# TMC2130.net
KiCad netlist of a schematic drawn in Altium Designer
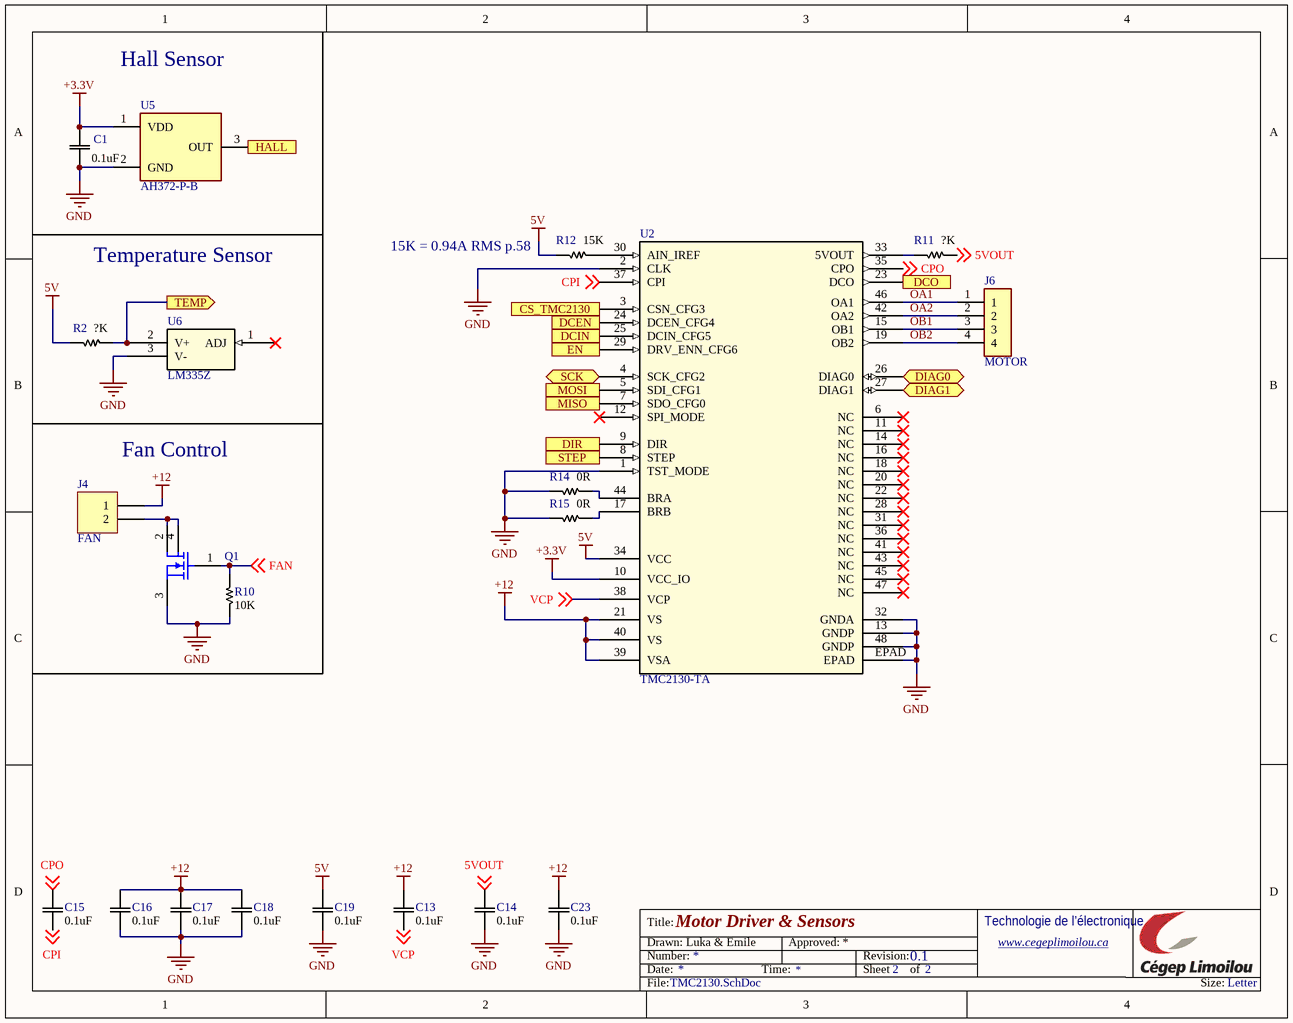
[diagram p0: TMC2130.SchDoc]

(export (version "E")
  (design (tool "Eeschema 10.0.6"))
  (components
    (comp (ref "C1")
      (value "0.1uF")
      (footprint "0603")
      (description "Capacitor SMD 0603")
      (fields
        (field (name "MANUFACTURER_PART_NUMBER") "12065A820JAT2A")
        (field (name "Comment") "Capacitor SMD")
        (field (name "COPYRIGHT") "Copyright (C) 2018 Accelerated Designs. All rights reserved")
      )
      (libsource (lib "Schematic_Emile") (part "Capacitor SMD"))
    )
    (comp (ref "C13")
      (value "0.1uF")
      (footprint "0603")
      (description "Capacitor SMD 0603")
      (fields
        (field (name "MANUFACTURER_PART_NUMBER") "12065A820JAT2A")
        (field (name "Comment") "Capacitor SMD")
        (field (name "COPYRIGHT") "Copyright (C) 2018 Accelerated Designs. All rights reserved")
      )
      (libsource (lib "Schematic_Emile") (part "Capacitor SMD"))
    )
    (comp (ref "C14")
      (value "0.1uF")
      (footprint "0603")
      (description "Capacitor SMD 0603")
      (fields
        (field (name "MANUFACTURER_PART_NUMBER") "12065A820JAT2A")
        (field (name "Comment") "Capacitor SMD")
        (field (name "COPYRIGHT") "Copyright (C) 2018 Accelerated Designs. All rights reserved")
      )
      (libsource (lib "Schematic_Emile") (part "Capacitor SMD"))
    )
    (comp (ref "C15")
      (value "0.1uF")
      (footprint "0603")
      (description "Capacitor SMD 0603")
      (fields
        (field (name "MANUFACTURER_PART_NUMBER") "12065A820JAT2A")
        (field (name "Comment") "Capacitor SMD")
        (field (name "COPYRIGHT") "Copyright (C) 2018 Accelerated Designs. All rights reserved")
      )
      (libsource (lib "Schematic_Emile") (part "Capacitor SMD"))
    )
    (comp (ref "C16")
      (value "0.1uF")
      (footprint "0603")
      (description "Capacitor SMD 0603")
      (fields
        (field (name "MANUFACTURER_PART_NUMBER") "12065A820JAT2A")
        (field (name "Comment") "Capacitor SMD")
        (field (name "COPYRIGHT") "Copyright (C) 2018 Accelerated Designs. All rights reserved")
      )
      (libsource (lib "Schematic_Emile") (part "Capacitor SMD"))
    )
    (comp (ref "C17")
      (value "0.1uF")
      (footprint "0603")
      (description "Capacitor SMD 0603")
      (fields
        (field (name "MANUFACTURER_PART_NUMBER") "12065A820JAT2A")
        (field (name "Comment") "Capacitor SMD")
        (field (name "COPYRIGHT") "Copyright (C) 2018 Accelerated Designs. All rights reserved")
      )
      (libsource (lib "Schematic_Emile") (part "Capacitor SMD"))
    )
    (comp (ref "C18")
      (value "0.1uF")
      (footprint "0603")
      (description "Capacitor SMD 0603")
      (fields
        (field (name "MANUFACTURER_PART_NUMBER") "12065A820JAT2A")
        (field (name "Comment") "Capacitor SMD")
        (field (name "COPYRIGHT") "Copyright (C) 2018 Accelerated Designs. All rights reserved")
      )
      (libsource (lib "Schematic_Emile") (part "Capacitor SMD"))
    )
    (comp (ref "C19")
      (value "0.1uF")
      (footprint "0603")
      (description "Capacitor SMD 0603")
      (fields
        (field (name "MANUFACTURER_PART_NUMBER") "12065A820JAT2A")
        (field (name "Comment") "Capacitor SMD")
        (field (name "COPYRIGHT") "Copyright (C) 2018 Accelerated Designs. All rights reserved")
      )
      (libsource (lib "Schematic_Emile") (part "Capacitor SMD"))
    )
    (comp (ref "C23")
      (value "0.1uF")
      (footprint "0603")
      (description "Capacitor SMD 0603")
      (fields
        (field (name "MANUFACTURER_PART_NUMBER") "12065A820JAT2A")
        (field (name "Comment") "Capacitor SMD")
        (field (name "COPYRIGHT") "Copyright (C) 2018 Accelerated Designs. All rights reserved")
      )
      (libsource (lib "Schematic_Emile") (part "Capacitor SMD"))
    )
    (comp (ref "J4")
      (value "FAN")
      (footprint "HDR1X2")
      (description "Header, 2-Pin")
      (fields (field (name "PUBLISHER") "Altium Limited"))
      (libsource (lib "Miscellaneous Connectors") (part "Header 2"))
    )
    (comp (ref "J6")
      (value "MOTOR")
      (footprint "JST 4POS 2.5mm 90°")
      (description "Connector")
      (fields
        (field (name "MANUFACTURER_PART_NUMBER") "S4B-XH-A(LF)(SN)")
        (field (name "RS PART NUMBER") "8201589P")
      )
      (libsource (lib "Schematic_Emile") (part "JST 4POS"))
    )
    (comp (ref "Q1")
      (value "MOSFET N-CH")
      (footprint "SOT223_M")
      (description "55V 7A SOT223")
      (libsource (lib "Schematic_Emile") (part "MOSFET N-CH"))
    )
    (comp (ref "R2")
      (value "?K")
      (footprint "0603")
      (description "Resistor 0603 SMD")
      (fields
        (field (name "MANUFACTURER_PART_NUMBER") "ERJ8CWFR024V")
        (field (name "Comment") "Resistor 0603")
        (field (name "COPYRIGHT") "Copyright (C) 2018 Accelerated Designs. All rights reserved")
      )
      (libsource (lib "Schematic_Emile") (part "Resistor 0603"))
    )
    (comp (ref "R10")
      (value "10K")
      (footprint "0603")
      (description "Resistor 0603 SMD")
      (fields
        (field (name "MANUFACTURER_PART_NUMBER") "ERJ8CWFR024V")
        (field (name "Comment") "Resistor 0603")
        (field (name "COPYRIGHT") "Copyright (C) 2018 Accelerated Designs. All rights reserved")
      )
      (libsource (lib "Schematic_Emile") (part "Resistor 0603"))
    )
    (comp (ref "R11")
      (value "?K")
      (footprint "0603")
      (description "Resistor 0603 SMD")
      (fields
        (field (name "MANUFACTURER_PART_NUMBER") "ERJ8CWFR024V")
        (field (name "Comment") "Resistor 0603")
        (field (name "COPYRIGHT") "Copyright (C) 2018 Accelerated Designs. All rights reserved")
      )
      (libsource (lib "Schematic_Emile") (part "Resistor 0603"))
    )
    (comp (ref "R12")
      (value "15K")
      (footprint "0603")
      (description "Resistor 0603 SMD")
      (fields
        (field (name "MANUFACTURER_PART_NUMBER") "ERJ8CWFR024V")
        (field (name "Comment") "Resistor 0603")
        (field (name "COPYRIGHT") "Copyright (C) 2018 Accelerated Designs. All rights reserved")
      )
      (libsource (lib "Schematic_Emile") (part "Resistor 0603"))
    )
    (comp (ref "R14")
      (value "0R")
      (footprint "0603")
      (description "Resistor 0603 SMD")
      (fields
        (field (name "MANUFACTURER_PART_NUMBER") "ERJ8CWFR024V")
        (field (name "Comment") "Resistor 0603")
        (field (name "COPYRIGHT") "Copyright (C) 2018 Accelerated Designs. All rights reserved")
      )
      (libsource (lib "Schematic_Emile") (part "Resistor 0603"))
    )
    (comp (ref "R15")
      (value "0R")
      (footprint "0603")
      (description "Resistor 0603 SMD")
      (fields
        (field (name "MANUFACTURER_PART_NUMBER") "ERJ8CWFR024V")
        (field (name "Comment") "Resistor 0603")
        (field (name "COPYRIGHT") "Copyright (C) 2018 Accelerated Designs. All rights reserved")
      )
      (libsource (lib "Schematic_Emile") (part "Resistor 0603"))
    )
    (comp (ref "U2")
      (value "TMC2130-TA")
      (footprint "eTQFP48_9x9")
      (description "Motor Driver TMC2130")
      (fields (field (name "COPYRIGHT") "Copyright (C) 2016 Accelerated Designs. All rights reserved"))
      (libsource (lib "Schematic_Emile") (part "TMC2130-TA"))
    )
    (comp (ref "U5")
      (value "AH372-P-B")
      (footprint "Footprint_Emile:AH372PB")
      (description "Hall Sensor")
      (fields (field (name "MOUSER PART NUMBER") "621-AH372-P-B") (field (name "RS PART NUMBER") "1333361P"))
      (libsource (lib "Schematic_Emile") (part "AH372-P-B"))
    )
    (comp (ref "U6")
      (value "LM335Z")
      (footprint "TO92")
      (description "Temperature Sensor")
      (fields (field (name "COPYRIGHT") "Copyright (C) 2018 Accelerated Designs. All rights reserved"))
      (libsource (lib "Schematic_Emile") (part "LM335Z"))
    )
  )
  (nets
    (net (code "1") (name "+3.3V") (class "Default")
      (node (ref "C1") (pin "2") (pinfunction "2_2") (pintype "passive"))
      (node (ref "U2") (pin "10") (pinfunction "VCC_IO_10") (pintype "power_in"))
      (node (ref "U5") (pin "1") (pinfunction "VDD_1") (pintype "passive"))
    )
    (net (code "2") (name "+12") (class "Default")
      (node (ref "C13") (pin "2") (pinfunction "2_2") (pintype "passive"))
      (node (ref "C16") (pin "2") (pinfunction "2_2") (pintype "passive"))
      (node (ref "C17") (pin "2") (pinfunction "2_2") (pintype "passive"))
      (node (ref "C18") (pin "2") (pinfunction "2_2") (pintype "passive"))
      (node (ref "C23") (pin "2") (pinfunction "2_2") (pintype "passive"))
      (node (ref "J4") (pin "1") (pinfunction "1_1") (pintype "passive"))
      (node (ref "U2") (pin "21") (pinfunction "VS_21") (pintype "power_in"))
      (node (ref "U2") (pin "39") (pinfunction "VSA_39") (pintype "power_in"))
      (node (ref "U2") (pin "40") (pinfunction "VS_40") (pintype "power_in"))
    )
    (net (code "3") (name "/CS_TMC2130") (class "Default")
      (node (ref "U2") (pin "3") (pinfunction "CSN_CFG3_3") (pintype "input"))
    )
    (net (code "4") (name "/DCEN") (class "Default")
      (node (ref "U2") (pin "24") (pinfunction "DCEN_CFG4_24") (pintype "input"))
    )
    (net (code "5") (name "/DCIN") (class "Default")
      (node (ref "U2") (pin "25") (pinfunction "DCIN_CFG5_25") (pintype "input"))
    )
    (net (code "6") (name "/DCO") (class "Default")
      (node (ref "U2") (pin "23") (pinfunction "DCO_23") (pintype "output"))
    )
    (net (code "7") (name "/DIAG0") (class "Default")
      (node (ref "U2") (pin "26") (pinfunction "DIAG0_26") (pintype "bidirectional"))
    )
    (net (code "8") (name "/DIAG1") (class "Default")
      (node (ref "U2") (pin "27") (pinfunction "DIAG1_27") (pintype "bidirectional"))
    )
    (net (code "9") (name "/DIR") (class "Default")
      (node (ref "U2") (pin "9") (pinfunction "DIR_9") (pintype "input"))
    )
    (net (code "10") (name "/EN") (class "Default")
      (node (ref "U2") (pin "29") (pinfunction "DRV_ENN_CFG6_29") (pintype "input"))
    )
    (net (code "11") (name "/HALL") (class "Default")
      (node (ref "U5") (pin "3") (pinfunction "OUT_3") (pintype "passive"))
    )
    (net (code "12") (name "/MISO") (class "Default")
      (node (ref "U2") (pin "7") (pinfunction "SDO_CFG0_7") (pintype "input"))
    )
    (net (code "13") (name "/MOSI") (class "Default")
      (node (ref "U2") (pin "5") (pinfunction "SDI_CFG1_5") (pintype "input"))
    )
    (net (code "14") (name "/OA1") (class "Default")
      (node (ref "J6") (pin "1") (pinfunction "1_1") (pintype "passive"))
      (node (ref "U2") (pin "46") (pinfunction "OA1_46") (pintype "output"))
    )
    (net (code "15") (name "/OA2") (class "Default")
      (node (ref "J6") (pin "2") (pinfunction "2_2") (pintype "passive"))
      (node (ref "U2") (pin "42") (pinfunction "OA2_42") (pintype "output"))
    )
    (net (code "16") (name "/OB1") (class "Default")
      (node (ref "J6") (pin "3") (pinfunction "3_3") (pintype "passive"))
      (node (ref "U2") (pin "15") (pinfunction "OB1_15") (pintype "output"))
    )
    (net (code "17") (name "/OB2") (class "Default")
      (node (ref "J6") (pin "4") (pinfunction "4_4") (pintype "passive"))
      (node (ref "U2") (pin "19") (pinfunction "OB2_19") (pintype "output"))
    )
    (net (code "18") (name "/SCK") (class "Default")
      (node (ref "U2") (pin "4") (pinfunction "SCK_CFG2_4") (pintype "input"))
    )
    (net (code "19") (name "/STEP") (class "Default")
      (node (ref "U2") (pin "8") (pinfunction "STEP_8") (pintype "input"))
    )
    (net (code "20") (name "/TEMP") (class "Default")
      (node (ref "R2") (pin "2") (pinfunction "2_2") (pintype "passive"))
      (node (ref "U6") (pin "2") (pinfunction "V+_2") (pintype "power_in"))
    )
    (net (code "21") (name "5V") (class "Default")
      (node (ref "C19") (pin "2") (pinfunction "2_2") (pintype "passive"))
      (node (ref "R12") (pin "1") (pinfunction "1_1") (pintype "passive"))
      (node (ref "R2") (pin "1") (pinfunction "1_1") (pintype "passive"))
      (node (ref "U2") (pin "34") (pinfunction "VCC_34") (pintype "power_in"))
    )
    (net (code "22") (name "5VOUT") (class "Default")
      (node (ref "C14") (pin "2") (pinfunction "2_2") (pintype "passive"))
      (node (ref "R11") (pin "2") (pinfunction "2_2") (pintype "passive"))
    )
    (net (code "23") (name "CPI") (class "Default")
      (node (ref "C15") (pin "1") (pinfunction "1_1") (pintype "passive"))
      (node (ref "U2") (pin "37") (pinfunction "CPI_37") (pintype "input"))
    )
    (net (code "24") (name "CPO") (class "Default")
      (node (ref "C15") (pin "2") (pinfunction "2_2") (pintype "passive"))
      (node (ref "U2") (pin "35") (pinfunction "CPO_35") (pintype "output"))
    )
    (net (code "25") (name "FAN") (class "Default")
      (node (ref "Q1") (pin "1") (pinfunction "G_1") (pintype "passive"))
      (node (ref "R10") (pin "2") (pinfunction "2_2") (pintype "passive"))
    )
    (net (code "26") (name "GND") (class "Default")
      (node (ref "C1") (pin "1") (pinfunction "1_1") (pintype "passive"))
      (node (ref "C14") (pin "1") (pinfunction "1_1") (pintype "passive"))
      (node (ref "C16") (pin "1") (pinfunction "1_1") (pintype "passive"))
      (node (ref "C17") (pin "1") (pinfunction "1_1") (pintype "passive"))
      (node (ref "C18") (pin "1") (pinfunction "1_1") (pintype "passive"))
      (node (ref "C19") (pin "1") (pinfunction "1_1") (pintype "passive"))
      (node (ref "C23") (pin "1") (pinfunction "1_1") (pintype "passive"))
      (node (ref "Q1") (pin "3") (pinfunction "S_3") (pintype "passive"))
      (node (ref "R10") (pin "1") (pinfunction "1_1") (pintype "passive"))
      (node (ref "R14") (pin "1") (pinfunction "1_1") (pintype "passive"))
      (node (ref "R15") (pin "1") (pinfunction "1_1") (pintype "passive"))
      (node (ref "U2") (pin "1") (pinfunction "TST_MODE_1") (pintype "input"))
      (node (ref "U2") (pin "13") (pinfunction "GNDP_13") (pintype "power_in"))
      (node (ref "U2") (pin "2") (pinfunction "CLK_2") (pintype "input"))
      (node (ref "U2") (pin "32") (pinfunction "GNDA_32") (pintype "power_in"))
      (node (ref "U2") (pin "48") (pinfunction "GNDP_48") (pintype "power_in"))
      (node (ref "U2") (pin "EPAD") (pinfunction "EPAD_EPAD") (pintype "passive"))
      (node (ref "U5") (pin "2") (pinfunction "GND_2") (pintype "passive"))
      (node (ref "U6") (pin "3") (pinfunction "V-_3") (pintype "power_in"))
    )
    (net (code "27") (name "Net-(J4-Pad2)") (class "Default")
      (node (ref "J4") (pin "2") (pinfunction "2_2") (pintype "passive"))
      (node (ref "Q1") (pin "2") (pinfunction "D_2") (pintype "passive"))
      (node (ref "Q1") (pin "4") (pinfunction "D_4") (pintype "passive"))
    )
    (net (code "28") (name "Net-(U2-5VOUT)") (class "Default")
      (node (ref "R11") (pin "1") (pinfunction "1_1") (pintype "passive"))
      (node (ref "U2") (pin "33") (pinfunction "5VOUT_33") (pintype "output"))
    )
    (net (code "29") (name "Net-(U2-AIN_IREF)") (class "Default")
      (node (ref "R12") (pin "2") (pinfunction "2_2") (pintype "passive"))
      (node (ref "U2") (pin "30") (pinfunction "AIN_IREF_30") (pintype "input"))
    )
    (net (code "30") (name "Net-(U2-BRA)") (class "Default")
      (node (ref "R14") (pin "2") (pinfunction "2_2") (pintype "passive"))
      (node (ref "U2") (pin "44") (pinfunction "BRA_44") (pintype "passive"))
    )
    (net (code "31") (name "Net-(U2-BRB)") (class "Default")
      (node (ref "R15") (pin "2") (pinfunction "2_2") (pintype "passive"))
      (node (ref "U2") (pin "17") (pinfunction "BRB_17") (pintype "passive"))
    )
    (net (code "32") (name "VCP") (class "Default")
      (node (ref "C13") (pin "1") (pinfunction "1_1") (pintype "passive"))
      (node (ref "U2") (pin "38") (pinfunction "VCP_38") (pintype "power_in"))
    )
    (net (code "33") (name "unconnected-(U2-NC-Pad6)") (class "Default")
      (node (ref "U2") (pin "6") (pinfunction "NC_6") (pintype "passive+no_connect"))
    )
    (net (code "34") (name "unconnected-(U2-NC-Pad11)") (class "Default")
      (node (ref "U2") (pin "11") (pinfunction "NC_11") (pintype "passive+no_connect"))
    )
    (net (code "35") (name "unconnected-(U2-NC-Pad14)") (class "Default")
      (node (ref "U2") (pin "14") (pinfunction "NC_14") (pintype "passive+no_connect"))
    )
    (net (code "36") (name "unconnected-(U2-NC-Pad16)") (class "Default")
      (node (ref "U2") (pin "16") (pinfunction "NC_16") (pintype "passive+no_connect"))
    )
    (net (code "37") (name "unconnected-(U2-NC-Pad18)") (class "Default")
      (node (ref "U2") (pin "18") (pinfunction "NC_18") (pintype "passive+no_connect"))
    )
    (net (code "38") (name "unconnected-(U2-NC-Pad20)") (class "Default")
      (node (ref "U2") (pin "20") (pinfunction "NC_20") (pintype "passive+no_connect"))
    )
    (net (code "39") (name "unconnected-(U2-NC-Pad22)") (class "Default")
      (node (ref "U2") (pin "22") (pinfunction "NC_22") (pintype "passive+no_connect"))
    )
    (net (code "40") (name "unconnected-(U2-NC-Pad28)") (class "Default")
      (node (ref "U2") (pin "28") (pinfunction "NC_28") (pintype "passive+no_connect"))
    )
    (net (code "41") (name "unconnected-(U2-NC-Pad31)") (class "Default")
      (node (ref "U2") (pin "31") (pinfunction "NC_31") (pintype "passive+no_connect"))
    )
    (net (code "42") (name "unconnected-(U2-NC-Pad36)") (class "Default")
      (node (ref "U2") (pin "36") (pinfunction "NC_36") (pintype "passive+no_connect"))
    )
    (net (code "43") (name "unconnected-(U2-NC-Pad41)") (class "Default")
      (node (ref "U2") (pin "41") (pinfunction "NC_41") (pintype "passive+no_connect"))
    )
    (net (code "44") (name "unconnected-(U2-NC-Pad43)") (class "Default")
      (node (ref "U2") (pin "43") (pinfunction "NC_43") (pintype "passive+no_connect"))
    )
    (net (code "45") (name "unconnected-(U2-NC-Pad45)") (class "Default")
      (node (ref "U2") (pin "45") (pinfunction "NC_45") (pintype "passive+no_connect"))
    )
    (net (code "46") (name "unconnected-(U2-NC-Pad47)") (class "Default")
      (node (ref "U2") (pin "47") (pinfunction "NC_47") (pintype "passive+no_connect"))
    )
    (net (code "47") (name "unconnected-(U2-SPI_MODE-Pad12)") (class "Default")
      (node (ref "U2") (pin "12") (pinfunction "SPI_MODE_12") (pintype "input+no_connect"))
    )
    (net (code "48") (name "unconnected-(U6-ADJ-Pad1)") (class "Default")
      (node (ref "U6") (pin "1") (pinfunction "ADJ_1") (pintype "input+no_connect"))
    )
  )
)
